# Interfaces.net
KiCad netlist of a schematic drawn in Altium Designer
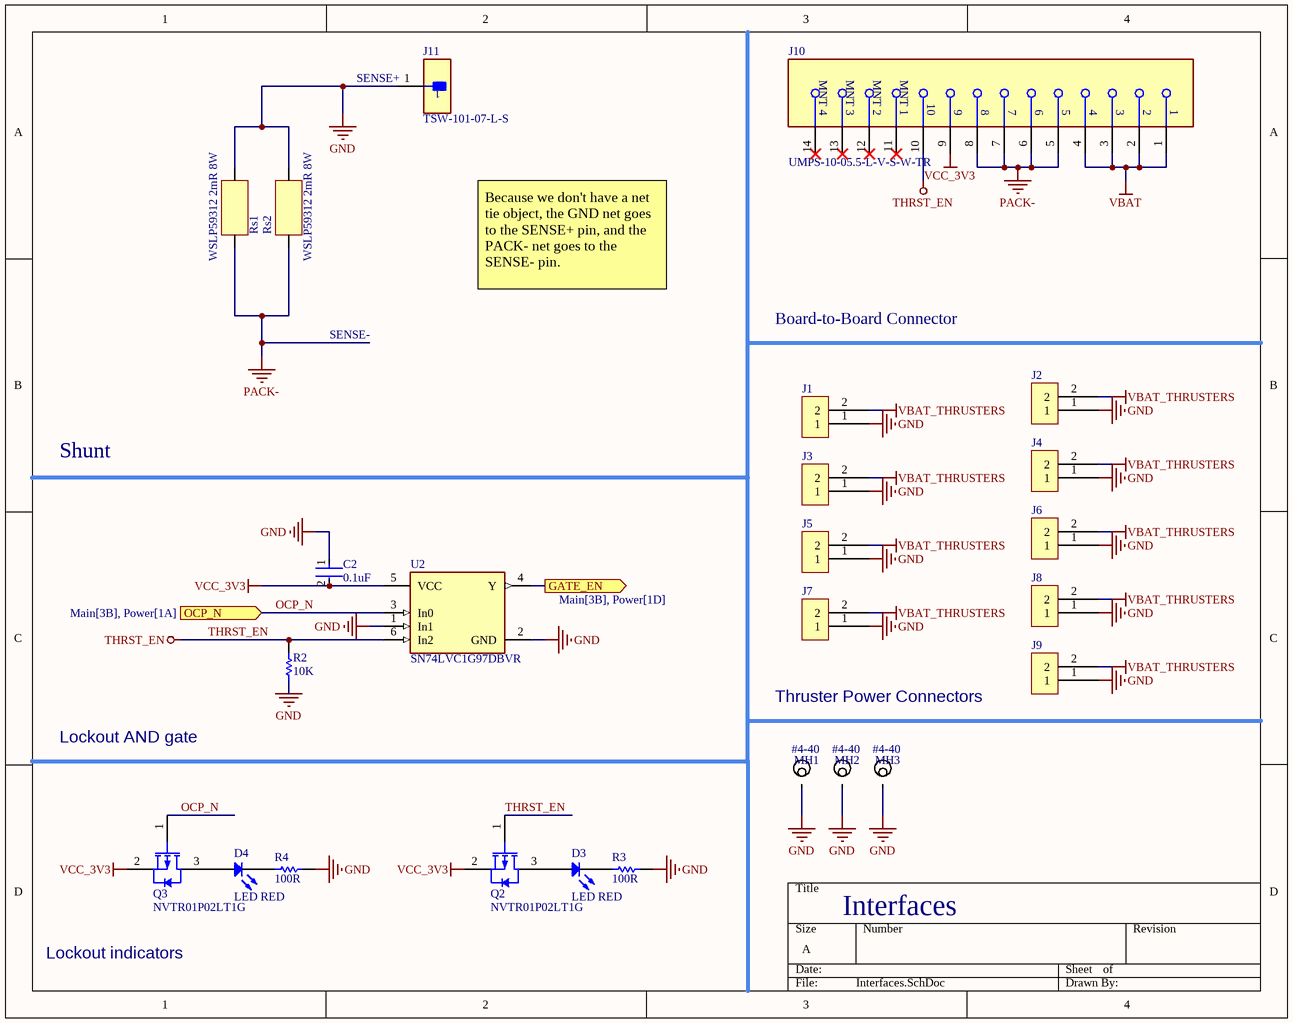
[diagram p0: Interfaces.SchDoc]

(export (version "E")
  (design (tool "Eeschema 10.0.6"))
  (components
    (comp (ref "C2")
      (value "0.1uF")
      (footprint "FP-C0603C-CF-MFG")
      (description "CAP CER 0.1UF 10V X7R 0603")
      (fields (field (name "TOLERANCE") "0.1") (field (name "MANUFACTURER PART NUMBER") "C0603C104K8RACTU"))
      (libsource (lib "Altium Content Vault") (part "b4654b650e69147ec39a6b967a45e02"))
    )
    (comp (ref "D3")
      (value "LED RED")
      (footprint "C0805")
      (description "led\r\n LTST-C171KRKT")
      (fields
        (field (name "MANUFACTURER") "Lite-On Inc.")
        (field (name "MANUFACTURER PART NUMBER") "LTST-C171KRKT")
      )
      (libsource (lib "CMR_Miscellaneous_Devices") (part "LED0"))
    )
    (comp (ref "D4")
      (value "LED RED")
      (footprint "C0805")
      (description "led\r\n LTST-C171KRKT")
      (fields
        (field (name "MANUFACTURER") "Lite-On Inc.")
        (field (name "MANUFACTURER PART NUMBER") "LTST-C171KRKT")
      )
      (libsource (lib "CMR_Miscellaneous_Devices") (part "LED0"))
    )
    (comp (ref "J1")
      (value "~")
      (footprint "2-pin Megafit RA")
      (libsource (lib "TAUV-Lib") (part "2-pin megafit"))
    )
    (comp (ref "J2")
      (value "~")
      (footprint "2-pin Megafit RA")
      (libsource (lib "TAUV-Lib") (part "2-pin megafit"))
    )
    (comp (ref "J3")
      (value "~")
      (footprint "2-pin Megafit RA")
      (libsource (lib "TAUV-Lib") (part "2-pin megafit"))
    )
    (comp (ref "J4")
      (value "~")
      (footprint "2-pin Megafit RA")
      (libsource (lib "TAUV-Lib") (part "2-pin megafit"))
    )
    (comp (ref "J5")
      (value "~")
      (footprint "2-pin Megafit RA")
      (libsource (lib "TAUV-Lib") (part "2-pin megafit"))
    )
    (comp (ref "J6")
      (value "~")
      (footprint "2-pin Megafit RA")
      (libsource (lib "TAUV-Lib") (part "2-pin megafit"))
    )
    (comp (ref "J7")
      (value "~")
      (footprint "2-pin Megafit RA")
      (libsource (lib "TAUV-Lib") (part "2-pin megafit"))
    )
    (comp (ref "J8")
      (value "~")
      (footprint "2-pin Megafit RA")
      (libsource (lib "TAUV-Lib") (part "2-pin megafit"))
    )
    (comp (ref "J9")
      (value "~")
      (footprint "2-pin Megafit RA")
      (libsource (lib "Tauv-Lib") (part "2-pin megafit"))
    )
    (comp (ref "J10")
      (value "UMPS-10-05.5-L-V-S-W-TR")
      (footprint "FP-UMPS-10-05_5-L-V-S-W-T-MFG")
      (description "CONN MPOWER 2MM FMALE 10POS GOLD")
      (libsource (lib "Altium Content Vault") (part "50ca1e906762132617f05a77d1e0c4c"))
    )
    (comp (ref "J11")
      (value "TSW-101-07-L-S")
      (footprint "FP-TSW-101-07-L-S-MFG")
      (description "CONN HEADER VERT 1POS")
      (libsource (lib "Altium Content Vault") (part "dd45045ce8184df9e99e12baf3f412c"))
    )
    (comp (ref "MH1")
      (value "#4-40")
      (footprint "Mounting Hole #4-40")
      (description "Mounting Hole for ANSI #4-40 w/ Flat Washer, Loose Fit")
      (libsource (lib "TAUV-Lib") (part "Mounting Hole #4-40, Loose Fit"))
    )
    (comp (ref "MH2")
      (value "#4-40")
      (footprint "Mounting Hole #4-40")
      (description "Mounting Hole for ANSI #4-40 w/ Flat Washer, Loose Fit")
      (libsource (lib "TAUV-Lib") (part "Mounting Hole #4-40, Loose Fit"))
    )
    (comp (ref "MH3")
      (value "#4-40")
      (footprint "Mounting Hole #4-40")
      (description "Mounting Hole for ANSI #4-40 w/ Flat Washer, Loose Fit")
      (libsource (lib "TAUV-Lib") (part "Mounting Hole #4-40, Loose Fit"))
    )
    (comp (ref "Q2")
      (value "NVTR01P02LT1G")
      (footprint "ONSC-SOT-23-3-318-08_V")
      (description "Power MOSFET, -20 V, -1.3 A, P-Channel, 3-Pin SOT-23, Pb-Free, Tape and Reel")
      (fields (field (name "MANUFACTURER") "On Semiconductor"))
      (libsource (lib "Altium Content Vault") (part "ONSC-PMOS-G1S2D3-3_D"))
    )
    (comp (ref "Q3")
      (value "NVTR01P02LT1G")
      (footprint "ONSC-SOT-23-3-318-08_V")
      (description "Power MOSFET, -20 V, -1.3 A, P-Channel, 3-Pin SOT-23, Pb-Free, Tape and Reel")
      (fields (field (name "MANUFACTURER") "On Semiconductor"))
      (libsource (lib "Altium Content Vault") (part "ONSC-PMOS-G1S2D3-3_D"))
    )
    (comp (ref "R2")
      (value "10K")
      (footprint "RESC0603(1608)_N")
      (description "10K 0.1W 5% 0603 (1608 Metric)  SMD")
      (fields (field (name "TOLERANCE") "5 %") (field (name "POWER") "0.1 W"))
      (libsource (lib "Altium Content Vault") (part "RES"))
    )
    (comp (ref "R3")
      (value "100R")
      (footprint "RESC1609X50X30NL10T20")
      (description "100R 0.1W 5%")
      (fields (field (name "PART NUMBER") "CRCW0603100RJNTA") (field (name "MANUFACTURER") "Vishay Dale"))
      (libsource (lib "Altium Content Vault") (part "RES"))
    )
    (comp (ref "R4")
      (value "100R")
      (footprint "RESC1609X50X30NL10T20")
      (description "100R 0.1W 5%")
      (fields (field (name "PART NUMBER") "CRCW0603100RJNTA") (field (name "MANUFACTURER") "Vishay Dale"))
      (libsource (lib "Altium Content Vault") (part "RES"))
    )
    (comp (ref "Rs1")
      (value "WSLP59312 2mR 8W")
      (footprint "WSLP59312L000FEA")
      (libsource (lib "Tauv-Lib") (part "WSLP59312L000FEA"))
    )
    (comp (ref "Rs2")
      (value "WSLP59312 2mR 8W")
      (footprint "WSLP59312L000FEA")
      (libsource (lib "Tauv-Lib") (part "WSLP59312L000FEA"))
    )
    (comp (ref "U2")
      (value "SN74LVC1G97DBVR")
      (footprint "FP-DBV0006A-MFG")
      (description "IC CONFIG MULT-FUNC GATE SOT23-6")
      (fields
        (field (name "OCTOPART") "https://octopart.com/sn74lvc1g97dbvr-texas+instruments-464842")
        (field (name "MANUFACTURER") "Texas Instruments")
      )
      (libsource (lib "Altium Content Vault") (part "a1876f62f2ab2790f28bb26e63f2887"))
    )
  )
  (nets
    (net (code "1") (name "/GATE_EN") (class "Default")
      (node (ref "U2") (pin "4") (pinfunction "Y_4") (pintype "output"))
    )
    (net (code "2") (name "/OCP_N") (class "Default")
      (node (ref "Q3") (pin "1") (pinfunction "G_1") (pintype "passive"))
      (node (ref "U2") (pin "3") (pinfunction "In0_3") (pintype "input"))
    )
    (net (code "3") (name "GND") (class "Default")
      (node (ref "C2") (pin "1") (pinfunction "1_1") (pintype "passive"))
      (node (ref "J1") (pin "1") (pinfunction "1_1") (pintype "passive"))
      (node (ref "J11") (pin "1") (pinfunction "1_1") (pintype "passive"))
      (node (ref "J2") (pin "1") (pinfunction "1_1") (pintype "passive"))
      (node (ref "J3") (pin "1") (pinfunction "1_1") (pintype "passive"))
      (node (ref "J4") (pin "1") (pinfunction "1_1") (pintype "passive"))
      (node (ref "J5") (pin "1") (pinfunction "1_1") (pintype "passive"))
      (node (ref "J6") (pin "1") (pinfunction "1_1") (pintype "passive"))
      (node (ref "J7") (pin "1") (pinfunction "1_1") (pintype "passive"))
      (node (ref "J8") (pin "1") (pinfunction "1_1") (pintype "passive"))
      (node (ref "J9") (pin "1") (pinfunction "1_1") (pintype "passive"))
      (node (ref "MH1") (pin "0") (pinfunction "0_0") (pintype "passive"))
      (node (ref "MH2") (pin "0") (pinfunction "0_0") (pintype "passive"))
      (node (ref "MH3") (pin "0") (pinfunction "0_0") (pintype "passive"))
      (node (ref "R2") (pin "2") (pinfunction "2_2") (pintype "passive"))
      (node (ref "R3") (pin "2") (pinfunction "2_2") (pintype "passive"))
      (node (ref "R4") (pin "2") (pinfunction "2_2") (pintype "passive"))
      (node (ref "Rs1") (pin "2") (pinfunction "2_2") (pintype "passive"))
      (node (ref "Rs2") (pin "2") (pinfunction "2_2") (pintype "passive"))
      (node (ref "U2") (pin "1") (pinfunction "In1_1") (pintype "input"))
      (node (ref "U2") (pin "2") (pinfunction "GND_2") (pintype "power_in"))
    )
    (net (code "4") (name "Net-(D3-A)") (class "Default")
      (node (ref "D3") (pin "2") (pinfunction "A_2") (pintype "passive"))
      (node (ref "Q2") (pin "3") (pinfunction "D_3") (pintype "passive"))
    )
    (net (code "5") (name "Net-(D3-K)") (class "Default")
      (node (ref "D3") (pin "1") (pinfunction "K_1") (pintype "passive"))
      (node (ref "R3") (pin "1") (pinfunction "1_1") (pintype "passive"))
    )
    (net (code "6") (name "Net-(D4-A)") (class "Default")
      (node (ref "D4") (pin "2") (pinfunction "A_2") (pintype "passive"))
      (node (ref "Q3") (pin "3") (pinfunction "D_3") (pintype "passive"))
    )
    (net (code "7") (name "Net-(D4-K)") (class "Default")
      (node (ref "D4") (pin "1") (pinfunction "K_1") (pintype "passive"))
      (node (ref "R4") (pin "1") (pinfunction "1_1") (pintype "passive"))
    )
    (net (code "8") (name "PACK-") (class "Default")
      (node (ref "J10") (pin "5") (pinfunction "5_5") (pintype "passive"))
      (node (ref "J10") (pin "6") (pinfunction "6_6") (pintype "passive"))
      (node (ref "J10") (pin "7") (pinfunction "7_7") (pintype "passive"))
      (node (ref "J10") (pin "8") (pinfunction "8_8") (pintype "passive"))
      (node (ref "Rs1") (pin "1") (pinfunction "1_1") (pintype "passive"))
      (node (ref "Rs2") (pin "1") (pinfunction "1_1") (pintype "passive"))
    )
    (net (code "9") (name "THRST_EN") (class "Default")
      (node (ref "J10") (pin "10") (pinfunction "10_10") (pintype "passive"))
      (node (ref "Q2") (pin "1") (pinfunction "G_1") (pintype "passive"))
      (node (ref "R2") (pin "1") (pinfunction "1_1") (pintype "passive"))
      (node (ref "U2") (pin "6") (pinfunction "In2_6") (pintype "input"))
    )
    (net (code "10") (name "VBAT") (class "Default")
      (node (ref "J10") (pin "1") (pinfunction "1_1") (pintype "passive"))
      (node (ref "J10") (pin "2") (pinfunction "2_2") (pintype "passive"))
      (node (ref "J10") (pin "3") (pinfunction "3_3") (pintype "passive"))
      (node (ref "J10") (pin "4") (pinfunction "4_4") (pintype "passive"))
    )
    (net (code "11") (name "VBAT_THRUSTERS") (class "Default")
      (node (ref "J1") (pin "2") (pinfunction "2_2") (pintype "passive"))
      (node (ref "J2") (pin "2") (pinfunction "2_2") (pintype "passive"))
      (node (ref "J3") (pin "2") (pinfunction "2_2") (pintype "passive"))
      (node (ref "J4") (pin "2") (pinfunction "2_2") (pintype "passive"))
      (node (ref "J5") (pin "2") (pinfunction "2_2") (pintype "passive"))
      (node (ref "J6") (pin "2") (pinfunction "2_2") (pintype "passive"))
      (node (ref "J7") (pin "2") (pinfunction "2_2") (pintype "passive"))
      (node (ref "J8") (pin "2") (pinfunction "2_2") (pintype "passive"))
      (node (ref "J9") (pin "2") (pinfunction "2_2") (pintype "passive"))
    )
    (net (code "12") (name "VCC_3V3") (class "Default")
      (node (ref "C2") (pin "2") (pinfunction "2_2") (pintype "passive"))
      (node (ref "J10") (pin "9") (pinfunction "9_9") (pintype "passive"))
      (node (ref "Q2") (pin "2") (pinfunction "S_2") (pintype "passive"))
      (node (ref "Q3") (pin "2") (pinfunction "S_2") (pintype "passive"))
      (node (ref "U2") (pin "5") (pinfunction "VCC_5") (pintype "power_in"))
    )
    (net (code "13") (name "unconnected-(J10-MNT_1-Pad11)") (class "Default")
      (node (ref "J10") (pin "11") (pinfunction "MNT_1_11") (pintype "passive+no_connect"))
    )
    (net (code "14") (name "unconnected-(J10-MNT_2-Pad12)") (class "Default")
      (node (ref "J10") (pin "12") (pinfunction "MNT_2_12") (pintype "passive+no_connect"))
    )
    (net (code "15") (name "unconnected-(J10-MNT_3-Pad13)") (class "Default")
      (node (ref "J10") (pin "13") (pinfunction "MNT_3_13") (pintype "passive+no_connect"))
    )
    (net (code "16") (name "unconnected-(J10-MNT_4-Pad14)") (class "Default")
      (node (ref "J10") (pin "14") (pinfunction "MNT_4_14") (pintype "passive+no_connect"))
    )
  )
)
